# buck.net
KiCad netlist of a schematic drawn in EAGLE
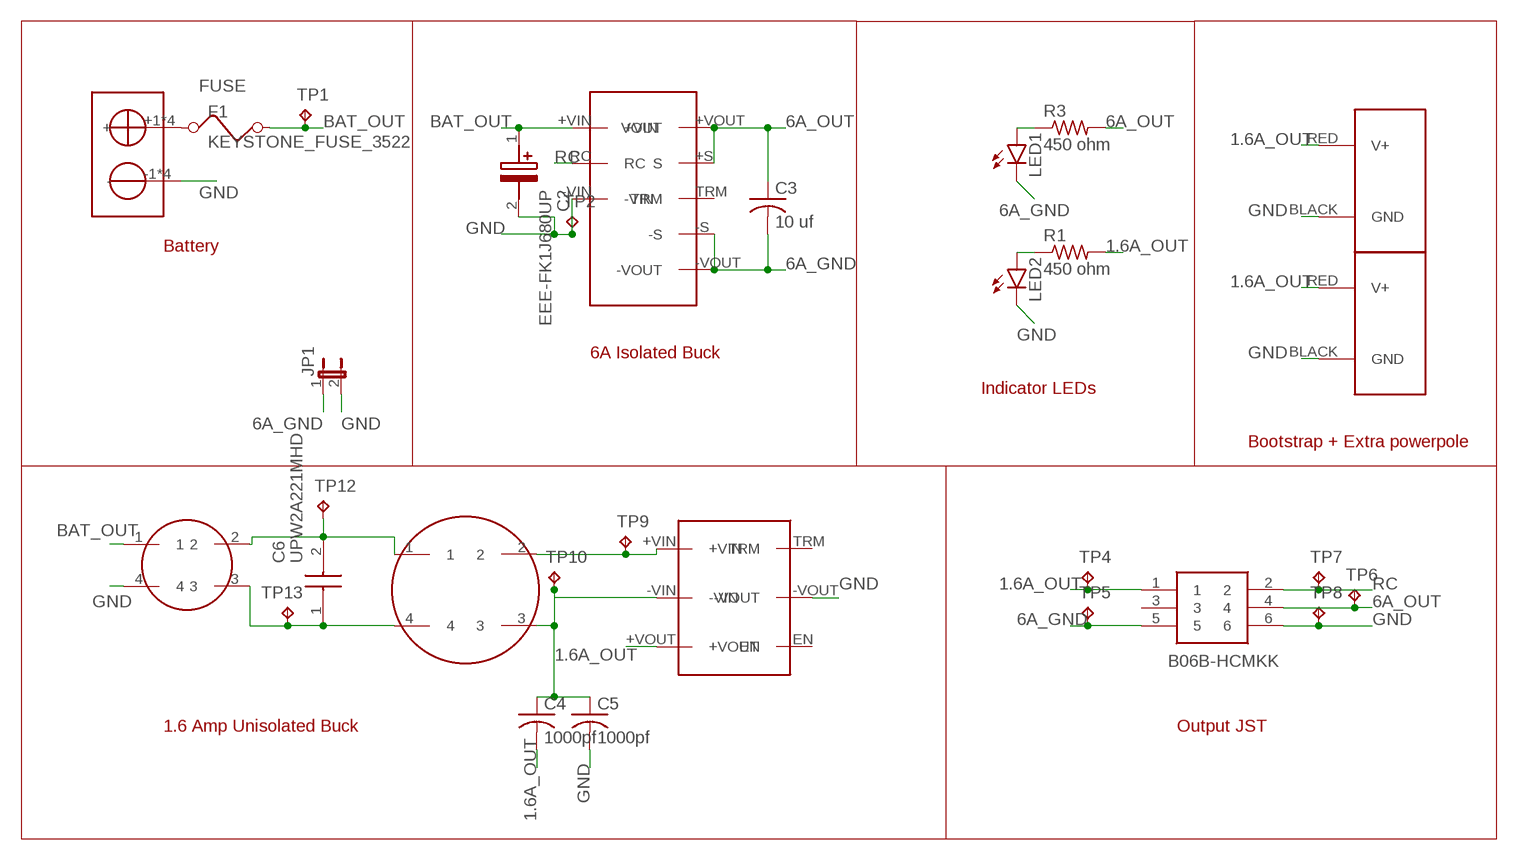
[diagram p0: schematic, sheet 1]

(export (version "E")
  (design (tool "Eeschema 10.0.6"))
  (components
    (comp (ref "BUCK150UH")
      (value "CMNMODECHOKE150UH")
      (footprint "eagle-import:CMNMODECHOKE150UH")
      (libsource (lib "eagle-import") (part "CMNMODECHOKE150UH"))
    )
    (comp (ref "C2")
      (value "EEE-FK1J680UP")
      (footprint "eagle-import:CAPAE830X1050N")
      (fields (field (name "MOUSER_PART_NUMBER") "667-EEE-FK1J680UP"))
      (libsource (lib "eagle-import") (part "EEE-FK1J680UP"))
    )
    (comp (ref "C3")
      (value "10 uf")
      (footprint "eagle-import:C0805")
      (libsource (lib "eagle-import") (part "C-USC0805"))
    )
    (comp (ref "C4")
      (value "1000pf")
      (footprint "eagle-import:C0805")
      (libsource (lib "eagle-import") (part "C-USC0805"))
    )
    (comp (ref "C5")
      (value "1000pf")
      (footprint "eagle-import:C0805")
      (libsource (lib "eagle-import") (part "C-USC0805"))
    )
    (comp (ref "C6")
      (value "UPW2A221MHD")
      (footprint "eagle-import:CAPPRD550W60D1050H1750")
      (fields (field (name "MOUSER_PART_NUMBER") "647-UPW2A221MHD"))
      (libsource (lib "eagle-import") (part "UPW2A221MHD"))
    )
    (comp (ref "CHOKEME")
      (value "CMNMODECHOKE1.2MH")
      (footprint "eagle-import:CMNMODECHOKE1.2MH")
      (libsource (lib "eagle-import") (part "CMNMODECHOKE1.2MH"))
    )
    (comp (ref "F1")
      (value "KEYSTONE_FUSE_3522")
      (footprint "eagle-import:KEYSTONE_FUSE_3522")
      (libsource (lib "eagle-import") (part "KEYSTONE_FUSE_3522"))
    )
    (comp (ref "J1")
      (value "B06B-HCMKK")
      (footprint "eagle-import:B06BHCMKK")
      (fields (field (name "MOUSER_PART_NUMBER") "306-B06B-HCMKK"))
      (libsource (lib "eagle-import") (part "B06B-HCMKK"))
    )
    (comp (ref "J2")
      (value "POWERPOLE_POWER45A_DRILL")
      (footprint "eagle-import:POWERPOLE_PAIR_45A_HOLE")
      (libsource (lib "eagle-import") (part "POWERPOLE_POWER45A_DRILL"))
    )
    (comp (ref "J3")
      (value "POWERPOLE_POWER45A_DRILL")
      (footprint "eagle-import:POWERPOLE_PAIR_45A_HOLE")
      (libsource (lib "eagle-import") (part "POWERPOLE_POWER45A_DRILL"))
    )
    (comp (ref "JP1")
      (value "JP1E")
      (footprint "eagle-import:JP1")
      (libsource (lib "eagle-import") (part "JP1E"))
    )
    (comp (ref "LED1")
      (value "LEDCHIP-LED0603")
      (footprint "eagle-import:CHIP-LED0603")
      (libsource (lib "eagle-import") (part "LEDCHIP-LED0603"))
    )
    (comp (ref "LED2")
      (value "LEDCHIP-LED0603")
      (footprint "eagle-import:CHIP-LED0603")
      (libsource (lib "eagle-import") (part "LEDCHIP-LED0603"))
    )
    (comp (ref "R1")
      (value "450 ohm")
      (footprint "eagle-import:R0805")
      (libsource (lib "eagle-import") (part "R-US_R0805"))
    )
    (comp (ref "R3")
      (value "450 ohm")
      (footprint "eagle-import:R0805")
      (libsource (lib "eagle-import") (part "R-US_R0805"))
    )
    (comp (ref "TP1")
      (value "TPPAD1-13")
      (footprint "eagle-import:P1-13")
      (libsource (lib "eagle-import") (part "TPPAD1-13"))
    )
    (comp (ref "TP2")
      (value "TPPAD1-13")
      (footprint "eagle-import:P1-13")
      (libsource (lib "eagle-import") (part "TPPAD1-13"))
    )
    (comp (ref "TP4")
      (value "TPPAD1-13")
      (footprint "eagle-import:P1-13")
      (libsource (lib "eagle-import") (part "TPPAD1-13"))
    )
    (comp (ref "TP5")
      (value "TPPAD1-13")
      (footprint "eagle-import:P1-13")
      (libsource (lib "eagle-import") (part "TPPAD1-13"))
    )
    (comp (ref "TP6")
      (value "TPPAD1-13")
      (footprint "eagle-import:P1-13")
      (libsource (lib "eagle-import") (part "TPPAD1-13"))
    )
    (comp (ref "TP7")
      (value "TPPAD1-13")
      (footprint "eagle-import:P1-13")
      (libsource (lib "eagle-import") (part "TPPAD1-13"))
    )
    (comp (ref "TP8")
      (value "TPPAD1-13")
      (footprint "eagle-import:P1-13")
      (libsource (lib "eagle-import") (part "TPPAD1-13"))
    )
    (comp (ref "TP9")
      (value "TPPAD1-13")
      (footprint "eagle-import:P1-13")
      (libsource (lib "eagle-import") (part "TPPAD1-13"))
    )
    (comp (ref "TP10")
      (value "TPPAD1-13")
      (footprint "eagle-import:P1-13")
      (libsource (lib "eagle-import") (part "TPPAD1-13"))
    )
    (comp (ref "TP12")
      (value "TPPAD1-13")
      (footprint "eagle-import:P1-13")
      (libsource (lib "eagle-import") (part "TPPAD1-13"))
    )
    (comp (ref "TP13")
      (value "TPPAD1-13")
      (footprint "eagle-import:P1-13")
      (libsource (lib "eagle-import") (part "TPPAD1-13"))
    )
    (comp (ref "U$1")
      (value "12V6ABUCKCONVERTER")
      (footprint "eagle-import:12V6ABUCKCONVERTER")
      (libsource (lib "eagle-import") (part "12V6ABUCKCONVERTER"))
    )
    (comp (ref "U$2")
      (value "SB50")
      (footprint "eagle-import:MINI-SB-50")
      (libsource (lib "eagle-import") (part "SB50"))
    )
    (comp (ref "U$3")
      (value "BUCK1.6A")
      (footprint "eagle-import:BUCK1.6A")
      (libsource (lib "eagle-import") (part "BUCK1.6A"))
    )
  )
  (nets
    (net (code "1") (name "/1.6A_OUT") (class "Default")
      (node (ref "C4") (pin "2") (pinfunction "2_2") (pintype "passive"))
      (node (ref "J1") (pin "1") (pinfunction "1_1") (pintype "bidirectional"))
      (node (ref "J2") (pin "RED") (pinfunction "V+_RED") (pintype "power_in"))
      (node (ref "J3") (pin "RED") (pinfunction "V+_RED") (pintype "power_in"))
      (node (ref "R1") (pin "2") (pinfunction "2_2") (pintype "passive"))
      (node (ref "TP4") (pin "TP") (pinfunction "TP_TP") (pintype "input"))
      (node (ref "U$3") (pin "+VOUT") (pinfunction "+VOUT_+VOUT") (pintype "bidirectional"))
    )
    (net (code "2") (name "/6A_GND") (class "Default")
      (node (ref "C3") (pin "2") (pinfunction "2_2") (pintype "passive"))
      (node (ref "J1") (pin "5") (pinfunction "5_5") (pintype "bidirectional"))
      (node (ref "JP1") (pin "1") (pinfunction "1_1") (pintype "passive"))
      (node (ref "LED1") (pin "C") (pinfunction "C_C") (pintype "passive"))
      (node (ref "TP5") (pin "TP") (pinfunction "TP_TP") (pintype "input"))
      (node (ref "U$1") (pin "-S") (pinfunction "-S_-S") (pintype "bidirectional"))
      (node (ref "U$1") (pin "-VOUT") (pinfunction "-VOUT_-VOUT") (pintype "bidirectional"))
    )
    (net (code "3") (name "/6A_OUT") (class "Default")
      (node (ref "C3") (pin "1") (pinfunction "1_1") (pintype "passive"))
      (node (ref "J1") (pin "4") (pinfunction "4_4") (pintype "bidirectional"))
      (node (ref "R3") (pin "2") (pinfunction "2_2") (pintype "passive"))
      (node (ref "TP6") (pin "TP") (pinfunction "TP_TP") (pintype "input"))
      (node (ref "U$1") (pin "+S") (pinfunction "S_+S") (pintype "bidirectional"))
      (node (ref "U$1") (pin "+VOUT") (pinfunction "VOUT_+VOUT") (pintype "bidirectional"))
    )
    (net (code "4") (name "/BAT_OUT") (class "Default")
      (node (ref "BUCK150UH") (pin "1") (pinfunction "1_1") (pintype "bidirectional"))
      (node (ref "C2") (pin "1") (pinfunction "+_1") (pintype "bidirectional"))
      (node (ref "F1") (pin "B1") (pinfunction "2_B1") (pintype "passive"))
      (node (ref "F1") (pin "B2") (pinfunction "2_B2") (pintype "passive"))
      (node (ref "TP1") (pin "TP") (pinfunction "TP_TP") (pintype "input"))
      (node (ref "U$1") (pin "+VIN") (pinfunction "+VIN_+VIN") (pintype "bidirectional"))
    )
    (net (code "6") (name "/FUSE") (class "Default")
      (node (ref "F1") (pin "A1") (pinfunction "1_A1") (pintype "passive"))
      (node (ref "F1") (pin "A2") (pinfunction "1_A2") (pintype "passive"))
      (node (ref "U$2") (pin "+1") (pinfunction "+_+1") (pintype "bidirectional"))
      (node (ref "U$2") (pin "+2") (pinfunction "+_+2") (pintype "bidirectional"))
      (node (ref "U$2") (pin "+3") (pinfunction "+_+3") (pintype "bidirectional"))
      (node (ref "U$2") (pin "+4") (pinfunction "+_+4") (pintype "bidirectional"))
    )
    (net (code "7") (name "/GND") (class "Default")
      (node (ref "BUCK150UH") (pin "4") (pinfunction "4_4") (pintype "bidirectional"))
      (node (ref "C2") (pin "2") (pinfunction "-_2") (pintype "bidirectional"))
      (node (ref "C5") (pin "2") (pinfunction "2_2") (pintype "passive"))
      (node (ref "J1") (pin "6") (pinfunction "6_6") (pintype "bidirectional"))
      (node (ref "J2") (pin "BLACK") (pinfunction "GND_BLACK") (pintype "power_in"))
      (node (ref "J3") (pin "BLACK") (pinfunction "GND_BLACK") (pintype "power_in"))
      (node (ref "JP1") (pin "2") (pinfunction "2_2") (pintype "passive"))
      (node (ref "LED2") (pin "C") (pinfunction "C_C") (pintype "passive"))
      (node (ref "TP2") (pin "TP") (pinfunction "TP_TP") (pintype "input"))
      (node (ref "TP8") (pin "TP") (pinfunction "TP_TP") (pintype "input"))
      (node (ref "U$1") (pin "-VIN") (pinfunction "-VIN_-VIN") (pintype "bidirectional"))
      (node (ref "U$2") (pin "-1") (pinfunction "-_-1") (pintype "bidirectional"))
      (node (ref "U$2") (pin "-2") (pinfunction "-_-2") (pintype "bidirectional"))
      (node (ref "U$2") (pin "-3") (pinfunction "-_-3") (pintype "bidirectional"))
      (node (ref "U$2") (pin "-4") (pinfunction "-_-4") (pintype "bidirectional"))
      (node (ref "U$3") (pin "-VOUT") (pinfunction "-VOUT_-VOUT") (pintype "bidirectional"))
    )
    (net (code "8") (name "/RC") (class "Default")
      (node (ref "J1") (pin "2") (pinfunction "2_2") (pintype "bidirectional"))
      (node (ref "TP7") (pin "TP") (pinfunction "TP_TP") (pintype "input"))
      (node (ref "U$1") (pin "RC") (pinfunction "RC_RC") (pintype "bidirectional"))
    )
    (net (code "9") (name "Net-(C4-Pad1)") (class "Default")
      (node (ref "C4") (pin "1") (pinfunction "1_1") (pintype "passive"))
      (node (ref "C5") (pin "1") (pinfunction "1_1") (pintype "passive"))
      (node (ref "CHOKEME") (pin "3") (pinfunction "3_3") (pintype "bidirectional"))
      (node (ref "TP10") (pin "TP") (pinfunction "TP_TP") (pintype "input"))
      (node (ref "U$3") (pin "-VIN") (pinfunction "-VIN_-VIN") (pintype "bidirectional"))
    )
    (net (code "10") (name "Net-(C6-+)") (class "Default")
      (node (ref "BUCK150UH") (pin "3") (pinfunction "3_3") (pintype "bidirectional"))
      (node (ref "C6") (pin "1") (pinfunction "+_1") (pintype "bidirectional"))
      (node (ref "CHOKEME") (pin "4") (pinfunction "4_4") (pintype "bidirectional"))
      (node (ref "TP13") (pin "TP") (pinfunction "TP_TP") (pintype "input"))
    )
    (net (code "11") (name "Net-(C6--)") (class "Default")
      (node (ref "BUCK150UH") (pin "2") (pinfunction "2_2") (pintype "bidirectional"))
      (node (ref "C6") (pin "2") (pinfunction "-_2") (pintype "bidirectional"))
      (node (ref "CHOKEME") (pin "1") (pinfunction "1_1") (pintype "bidirectional"))
      (node (ref "TP12") (pin "TP") (pinfunction "TP_TP") (pintype "input"))
    )
    (net (code "12") (name "Net-(CHOKEME-Pad2)") (class "Default")
      (node (ref "CHOKEME") (pin "2") (pinfunction "2_2") (pintype "bidirectional"))
      (node (ref "TP9") (pin "TP") (pinfunction "TP_TP") (pintype "input"))
      (node (ref "U$3") (pin "+VIN") (pinfunction "+VIN_+VIN") (pintype "bidirectional"))
    )
    (net (code "13") (name "Net-(LED1-PadA)") (class "Default")
      (node (ref "LED1") (pin "A") (pinfunction "A_A") (pintype "passive"))
      (node (ref "R3") (pin "1") (pinfunction "1_1") (pintype "passive"))
    )
    (net (code "14") (name "Net-(LED2-PadA)") (class "Default")
      (node (ref "LED2") (pin "A") (pinfunction "A_A") (pintype "passive"))
      (node (ref "R1") (pin "1") (pinfunction "1_1") (pintype "passive"))
    )
    (net (code "15") (name "unconnected-(J1-Pad3)") (class "Default")
      (node (ref "J1") (pin "3") (pinfunction "3_3") (pintype "bidirectional"))
    )
    (net (code "16") (name "unconnected-(U$1-PadTRM)") (class "Default")
      (node (ref "U$1") (pin "TRM") (pinfunction "TRM_TRM") (pintype "bidirectional"))
    )
    (net (code "17") (name "unconnected-(U$3-PadEN)") (class "Default")
      (node (ref "U$3") (pin "EN") (pinfunction "EN_EN") (pintype "bidirectional"))
    )
    (net (code "18") (name "unconnected-(U$3-PadTRM)") (class "Default")
      (node (ref "U$3") (pin "TRM") (pinfunction "TRM_TRM") (pintype "bidirectional"))
    )
  )
)
